# 12_Clock_2.net
KiCad netlist of a schematic drawn in Altium Designer
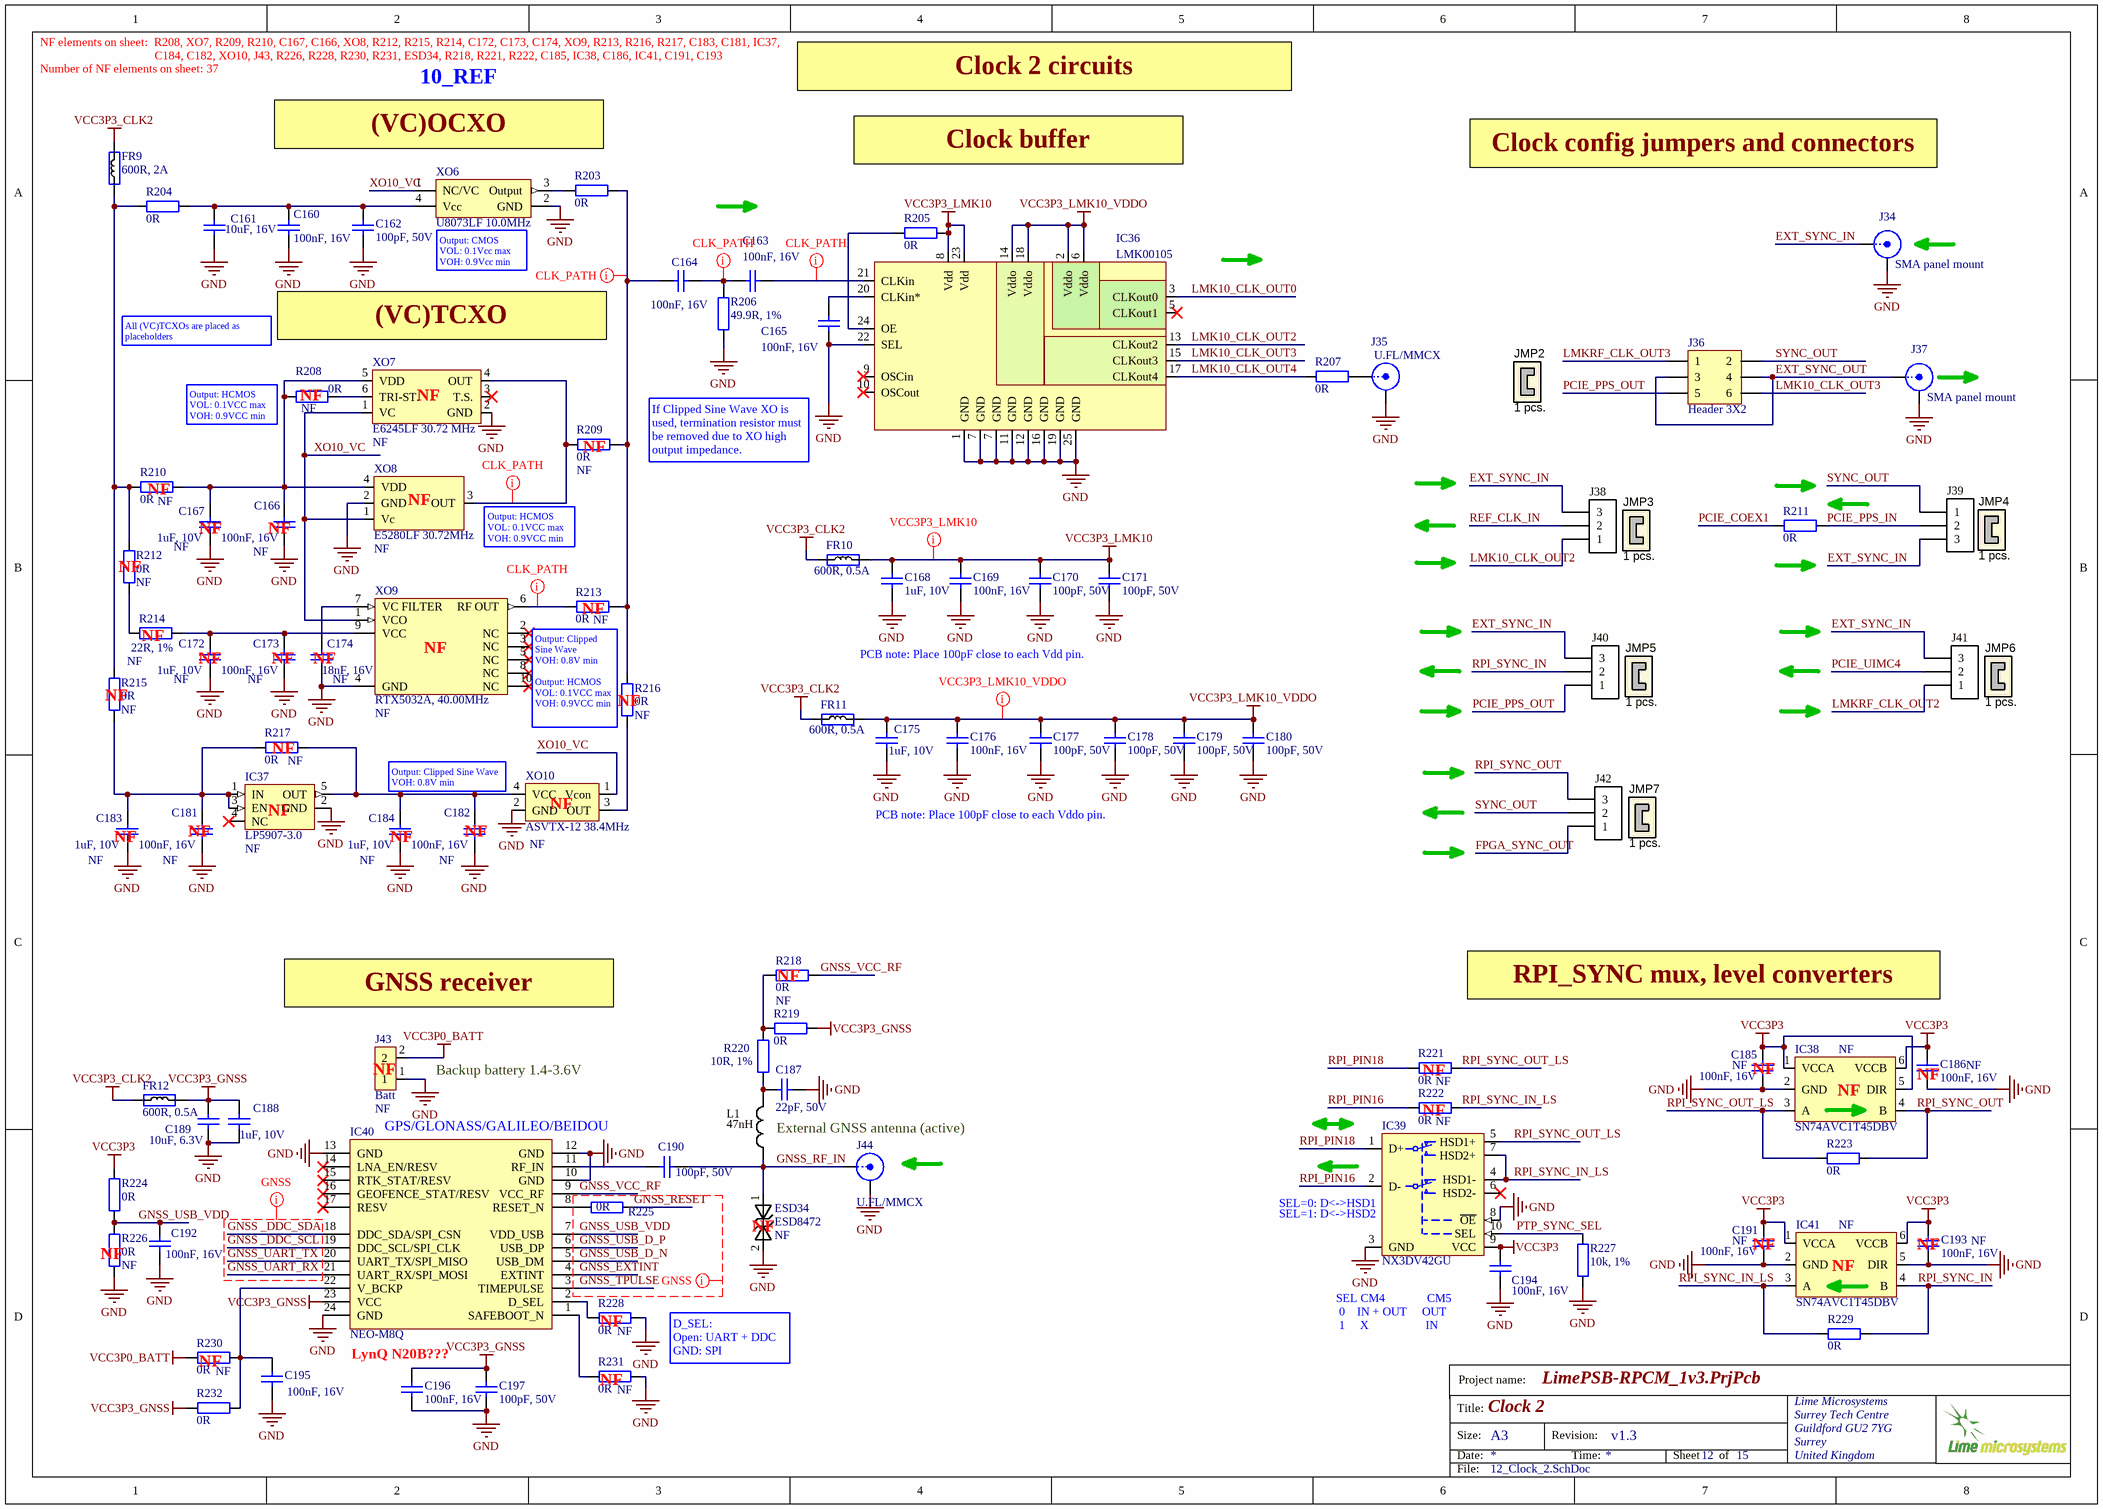
[diagram p0: 12_Clock_2.SchDoc]

(export (version "E")
  (design (tool "Eeschema 10.0.6"))
  (components
    (comp (ref "C160")
      (value "100nF, 16V")
      (footprint "CAP0402")
      (fields
        (field (name "MANUFACTURER") "Murata Electronics")
        (field (name "TOLERANCE") "10 %")
        (field (name "MANUFACTURER PART NUMBER") "GRM155R71C104KA88D")
      )
      (libsource (lib "LimeMicroAltiumLib_schLib") (part "Cap_0402"))
    )
    (comp (ref "C161")
      (value "10uF, 16V")
      (footprint "CAP0603")
      (fields (field (name "MANUFACTURER") "Yageo") (field (name "TOLERANCE") "±20%"))
      (libsource (lib "LimeMicroAltiumLib_schLib") (part "Cap_0603"))
    )
    (comp (ref "C162")
      (value "100pF, 50V")
      (footprint "CAP0402")
      (fields (field (name "TOLERANCE") "±5%") (field (name "MANUFACTURER") "Yageo"))
      (libsource (lib "LimeMicroAltiumLib_schLib") (part "Cap_0402"))
    )
    (comp (ref "C163")
      (value "100nF, 16V")
      (footprint "CAP0402")
      (fields
        (field (name "MANUFACTURER") "Murata Electronics")
        (field (name "TOLERANCE") "10 %")
        (field (name "MANUFACTURER PART NUMBER") "GRM155R71C104KA88D")
      )
      (libsource (lib "LimeMicroAltiumLib_schLib") (part "Cap_0402"))
    )
    (comp (ref "C164")
      (value "100nF, 16V")
      (footprint "CAP0402")
      (fields
        (field (name "MANUFACTURER") "Murata Electronics")
        (field (name "TOLERANCE") "10 %")
        (field (name "MANUFACTURER PART NUMBER") "GRM155R71C104KA88D")
      )
      (libsource (lib "LimeMicroAltiumLib_schLib") (part "Cap_0402"))
    )
    (comp (ref "C165")
      (value "100nF, 16V")
      (footprint "CAP0402")
      (fields
        (field (name "MANUFACTURER") "Murata Electronics")
        (field (name "TOLERANCE") "10 %")
        (field (name "MANUFACTURER PART NUMBER") "GRM155R71C104KA88D")
      )
      (libsource (lib "LimeMicroAltiumLib_schLib") (part "Cap_0402"))
    )
    (comp (ref "C166")
      (value "100nF, 16V")
      (footprint "CAP0402")
      (fields
        (field (name "ASSEMBLY INFO") "NF")
        (field (name "MANUFACTURER") "Murata Electronics")
        (field (name "TOLERANCE") "10 %")
        (field (name "MANUFACTURER PART NUMBER") "GRM155R71C104KA88D")
      )
      (libsource (lib "LimeMicroAltiumLib_schLib") (part "Cap_0402"))
    )
    (comp (ref "C167")
      (value "1uF, 10V")
      (footprint "CAP0402")
      (description "CAP CER 1UF 10V X5R 0402")
      (fields (field (name "ASSEMBLY INFO") "NF") (field (name "MANUFACTURER") "Yageo"))
      (libsource (lib "LimeMicroAltiumLib_schLib") (part "Cap_0402"))
    )
    (comp (ref "C168")
      (value "1uF, 10V")
      (footprint "CAP0402")
      (description "CAP CER 1UF 10V X5R 0402")
      (fields (field (name "MANUFACTURER") "Yageo") (field (name "TOLERANCE") "±20%"))
      (libsource (lib "LimeMicroAltiumLib_schLib") (part "Cap_0402"))
    )
    (comp (ref "C169")
      (value "100nF, 16V")
      (footprint "CAP0402")
      (fields
        (field (name "MANUFACTURER") "Murata Electronics")
        (field (name "TOLERANCE") "10 %")
        (field (name "MANUFACTURER PART NUMBER") "GRM155R71C104KA88D")
      )
      (libsource (lib "LimeMicroAltiumLib_schLib") (part "Cap_0402"))
    )
    (comp (ref "C170")
      (value "100pF, 50V")
      (footprint "CAP0402")
      (fields (field (name "MANUFACTURER") "Yageo") (field (name "TOLERANCE") "±5%"))
      (libsource (lib "LimeMicroAltiumLib_schLib") (part "Cap_0402"))
    )
    (comp (ref "C171")
      (value "100pF, 50V")
      (footprint "CAP0402")
      (fields (field (name "MANUFACTURER") "Yageo") (field (name "TOLERANCE") "±5%"))
      (libsource (lib "LimeMicroAltiumLib_schLib") (part "Cap_0402"))
    )
    (comp (ref "C172")
      (value "1uF, 10V")
      (footprint "CAP0402")
      (description "CAP CER 1UF 10V X5R 0402")
      (fields (field (name "ASSEMBLY INFO") "NF") (field (name "MANUFACTURER") "Yageo"))
      (libsource (lib "LimeMicroAltiumLib_schLib") (part "Cap_0402"))
    )
    (comp (ref "C173")
      (value "100nF, 16V")
      (footprint "CAP0402")
      (fields
        (field (name "ASSEMBLY INFO") "NF")
        (field (name "MANUFACTURER") "Murata Electronics")
        (field (name "TOLERANCE") "10 %")
        (field (name "MANUFACTURER PART NUMBER") "GRM155R71C104KA88D")
      )
      (libsource (lib "LimeMicroAltiumLib_schLib") (part "Cap_0402"))
    )
    (comp (ref "C174")
      (value "18nF, 16V")
      (footprint "CAP0402")
      (fields
        (field (name "ASSEMBLY INFO") "NF")
        (field (name "MANUFACTURER") "Yageo")
        (field (name "TOLERANCE") "±10%")
      )
      (libsource (lib "LimeMicroAltiumLib_schLib") (part "Cap_0402"))
    )
    (comp (ref "C175")
      (value "1uF, 10V")
      (footprint "CAP0402")
      (description "CAP CER 1UF 10V X5R 0402")
      (fields (field (name "MANUFACTURER") "Yageo") (field (name "TOLERANCE") "±20%"))
      (libsource (lib "LimeMicroAltiumLib_schLib") (part "Cap_0402"))
    )
    (comp (ref "C176")
      (value "100nF, 16V")
      (footprint "CAP0402")
      (fields
        (field (name "MANUFACTURER") "Murata Electronics")
        (field (name "TOLERANCE") "10 %")
        (field (name "MANUFACTURER PART NUMBER") "GRM155R71C104KA88D")
      )
      (libsource (lib "LimeMicroAltiumLib_schLib") (part "Cap_0402"))
    )
    (comp (ref "C177")
      (value "100pF, 50V")
      (footprint "CAP0402")
      (fields (field (name "MANUFACTURER") "Yageo") (field (name "TOLERANCE") "±5%"))
      (libsource (lib "LimeMicroAltiumLib_schLib") (part "Cap_0402"))
    )
    (comp (ref "C178")
      (value "100pF, 50V")
      (footprint "CAP0402")
      (fields (field (name "MANUFACTURER") "Yageo") (field (name "TOLERANCE") "±5%"))
      (libsource (lib "LimeMicroAltiumLib_schLib") (part "Cap_0402"))
    )
    (comp (ref "C179")
      (value "100pF, 50V")
      (footprint "CAP0402")
      (fields (field (name "MANUFACTURER") "Yageo") (field (name "TOLERANCE") "±5%"))
      (libsource (lib "LimeMicroAltiumLib_schLib") (part "Cap_0402"))
    )
    (comp (ref "C180")
      (value "100pF, 50V")
      (footprint "CAP0402")
      (fields (field (name "MANUFACTURER") "Yageo") (field (name "TOLERANCE") "±5%"))
      (libsource (lib "LimeMicroAltiumLib_schLib") (part "Cap_0402"))
    )
    (comp (ref "C181")
      (value "100nF, 16V")
      (footprint "CAP0402")
      (fields
        (field (name "ASSEMBLY INFO") "NF")
        (field (name "MANUFACTURER") "Murata Electronics")
        (field (name "TOLERANCE") "10 %")
        (field (name "MANUFACTURER PART NUMBER") "GRM155R71C104KA88D")
      )
      (libsource (lib "") (part "Cap_0402_1"))
    )
    (comp (ref "C182")
      (value "100nF, 16V")
      (footprint "CAP0402")
      (fields
        (field (name "ASSEMBLY INFO") "NF")
        (field (name "MANUFACTURER") "Murata Electronics")
        (field (name "TOLERANCE") "10 %")
        (field (name "MANUFACTURER PART NUMBER") "GRM155R71C104KA88D")
      )
      (libsource (lib "") (part "Cap_0402_1"))
    )
    (comp (ref "C183")
      (value "1uF, 10V")
      (footprint "CAP0402")
      (fields (field (name "ASSEMBLY INFO") "NF") (field (name "MANUFACTURER") "Yageo"))
      (libsource (lib "") (part "Cap_0402_1"))
    )
    (comp (ref "C184")
      (value "1uF, 10V")
      (footprint "CAP0402")
      (fields (field (name "ASSEMBLY INFO") "NF") (field (name "MANUFACTURER") "Yageo"))
      (libsource (lib "") (part "Cap_0402_1"))
    )
    (comp (ref "C185")
      (value "100nF, 16V")
      (footprint "CAP0402")
      (fields
        (field (name "ASSEMBLY INFO") "NF")
        (field (name "MANUFACTURER") "Murata Electronics")
        (field (name "TOLERANCE") "10 %")
        (field (name "MANUFACTURER PART NUMBER") "GRM155R71C104KA88D")
      )
      (libsource (lib "LimeMicroAltiumLib_schLib") (part "Cap_0402"))
    )
    (comp (ref "C186")
      (value "100nF, 16V")
      (footprint "CAP0402")
      (fields
        (field (name "ASSEMBLY INFO") "NF")
        (field (name "MANUFACTURER") "Murata Electronics")
        (field (name "TOLERANCE") "10 %")
        (field (name "MANUFACTURER PART NUMBER") "GRM155R71C104KA88D")
      )
      (libsource (lib "LimeMicroAltiumLib_schLib") (part "Cap_0402"))
    )
    (comp (ref "C187")
      (value "22pF, 50V")
      (footprint "CAP0402")
      (fields (field (name "TOLERANCE") "±5%") (field (name "MANUFACTURER") "Yageo"))
      (libsource (lib "LimeMicroAltiumLib_schLib") (part "Cap_0402"))
    )
    (comp (ref "C188")
      (value "1uF, 10V")
      (footprint "CAP0402")
      (description "CAP CER 1UF 10V X5R 0402")
      (fields (field (name "MANUFACTURER") "Yageo") (field (name "TOLERANCE") "±20%"))
      (libsource (lib "LimeMicroAltiumLib_schLib") (part "Cap_0402"))
    )
    (comp (ref "C189")
      (value "10uF, 6.3V")
      (footprint "CAP0603")
      (fields (field (name "TOLERANCE") "±20%") (field (name "MANUFACTURER") "Yageo"))
      (libsource (lib "LimeFPGAboard_schLib") (part "Cap_0603"))
    )
    (comp (ref "C190")
      (value "100pF, 50V")
      (footprint "CAP0402")
      (fields (field (name "TOLERANCE") "±5%") (field (name "MANUFACTURER") "Yageo"))
      (libsource (lib "LimeMicroAltiumLib_schLib") (part "Cap_0402"))
    )
    (comp (ref "C191")
      (value "100nF, 16V")
      (footprint "CAP0402")
      (fields
        (field (name "ASSEMBLY INFO") "NF")
        (field (name "MANUFACTURER") "Murata Electronics")
        (field (name "TOLERANCE") "10 %")
        (field (name "MANUFACTURER PART NUMBER") "GRM155R71C104KA88D")
      )
      (libsource (lib "LimeMicroAltiumLib_schLib") (part "Cap_0402"))
    )
    (comp (ref "C192")
      (value "100nF, 16V")
      (footprint "CAP0402")
      (fields
        (field (name "TOLERANCE") "10 %")
        (field (name "MANUFACTURER") "Murata Electronics")
        (field (name "MANUFACTURER PART NUMBER") "GRM155R71C104KA88D")
      )
      (libsource (lib "LimeFPGAboard_schLib") (part "Cap_0603"))
    )
    (comp (ref "C193")
      (value "100nF, 16V")
      (footprint "CAP0402")
      (fields
        (field (name "ASSEMBLY INFO") "NF")
        (field (name "MANUFACTURER") "Murata Electronics")
        (field (name "TOLERANCE") "10 %")
        (field (name "MANUFACTURER PART NUMBER") "GRM155R71C104KA88D")
      )
      (libsource (lib "LimeMicroAltiumLib_schLib") (part "Cap_0402"))
    )
    (comp (ref "C194")
      (value "100nF, 16V")
      (footprint "CAP0402")
      (fields
        (field (name "MANUFACTURER") "Murata Electronics")
        (field (name "TOLERANCE") "10 %")
        (field (name "MANUFACTURER PART NUMBER") "GRM155R71C104KA88D")
      )
      (libsource (lib "LimeMicroAltiumLib_schLib") (part "Cap_0402"))
    )
    (comp (ref "C195")
      (value "100nF, 16V")
      (footprint "CAP0402")
      (fields
        (field (name "TOLERANCE") "10 %")
        (field (name "MANUFACTURER") "Murata Electronics")
        (field (name "MANUFACTURER PART NUMBER") "GRM155R71C104KA88D")
      )
      (libsource (lib "LimeFPGAboard_schLib") (part "Cap_0603"))
    )
    (comp (ref "C196")
      (value "100nF, 16V")
      (footprint "CAP0402")
      (fields
        (field (name "MANUFACTURER") "Murata Electronics")
        (field (name "TOLERANCE") "10 %")
        (field (name "MANUFACTURER PART NUMBER") "GRM155R71C104KA88D")
      )
      (libsource (lib "LimeMicroAltiumLib_schLib") (part "Cap_0402"))
    )
    (comp (ref "C197")
      (value "100pF, 50V")
      (footprint "CAP0402")
      (fields (field (name "TOLERANCE") "±5%") (field (name "MANUFACTURER") "Yageo"))
      (libsource (lib "LimeMicroAltiumLib_schLib") (part "Cap_0402"))
    )
    (comp (ref "ESD34")
      (value "ESD8472")
      (footprint "ESD8472_X3DFN2")
      (fields
        (field (name "MANUFACTURER") "ON Semiconductor")
        (field (name "MANUFACTURER PART NUMBER") "ESD8472MUT5G")
        (field (name "ASSEMBLY INFO") "NF")
      )
      (libsource (lib "LimeMicroAltiumLib_schLib") (part "ESD8472"))
    )
    (comp (ref "FR9")
      (value "600R, 2A")
      (footprint "RES0805")
      (fields (field (name "MANUFACTURER") "TDK Corporation"))
      (libsource (lib "LimeFPGAboard_schLib") (part "Ferrite"))
    )
    (comp (ref "FR10")
      (value "600R, 0.5A")
      (footprint "RES0402")
      (fields (field (name "MANUFACTURER") "Murata") (field (name "TOLERANCE") "25%"))
      (libsource (lib "LimeMicroAltiumLib_schLib") (part "Ferrite"))
    )
    (comp (ref "FR11")
      (value "600R, 0.5A")
      (footprint "RES0402")
      (fields (field (name "MANUFACTURER") "Murata") (field (name "TOLERANCE") "25%"))
      (libsource (lib "LimeMicroAltiumLib_schLib") (part "Ferrite"))
    )
    (comp (ref "FR12")
      (value "600R, 0.5A")
      (footprint "RES0402")
      (fields (field (name "MANUFACTURER") "Murata") (field (name "TOLERANCE") "25%"))
      (libsource (lib "LimeMicroAltiumLib_schLib") (part "Ferrite"))
    )
    (comp (ref "IC36")
      (value "LMK00105")
      (footprint "LMK00105SQ")
      (fields (field (name "MANUFACTURER") "Texas Instruments"))
      (libsource (lib "LimeMicroAltiumLib_schLib") (part "LMK00105"))
    )
    (comp (ref "IC37")
      (value "LP5907-3.0")
      (footprint "SOT23-5")
      (fields (field (name "MANUFACTURER") "Texas Instruments") (field (name "ASSEMBLY INFO") "NF"))
      (libsource (lib "LimeMicroAltiumLib_schLib_r01") (part "LP5907"))
    )
    (comp (ref "IC38")
      (value "SN74AVC1T45DBV")
      (footprint "SOT23-6")
      (fields (field (name "ASSEMBLY INFO") "NF") (field (name "MANUFACTURER") "Texas Instruments"))
      (libsource (lib "LimeMicroAltiumLib_schLib_r04") (part "SN74AVC1T45DBV"))
    )
    (comp (ref "IC39")
      (value "NX3DV42GU")
      (footprint "FSUSB42UMX")
      (fields (field (name "MANUFACTURER") "NXP Semiconductors"))
      (libsource (lib "LimeMicroAltiumLib_schLib_r01") (part "FSUSB42UMX"))
    )
    (comp (ref "IC40")
      (value "NEO-M8Q")
      (footprint "NEO-7M/8M")
      (description "GNSS engine for GPS/QZSS, GLONASS")
      (fields (field (name "MANUFACTURER") "U-blox"))
      (libsource (lib "LimeMicroAltiumLib_schLib") (part "NEO-M8P_M8M"))
    )
    (comp (ref "IC41")
      (value "SN74AVC1T45DBV")
      (footprint "SOT23-6")
      (fields (field (name "ASSEMBLY INFO") "NF") (field (name "MANUFACTURER") "Texas Instruments"))
      (libsource (lib "LimeMicroAltiumLib_schLib_r04") (part "SN74AVC1T45DBV"))
    )
    (comp (ref "J34")
      (value "SMA panel mount")
      (footprint "SMA_connector_side")
      (description "CONN SMA JACK STR 50OHM EDGE MNT")
      (fields (field (name "MANUFACTURER") "Linx"))
      (libsource (lib "LimeMicroAltiumLib_schLib") (part "RF_IF_connector"))
    )
    (comp (ref "J35")
      (value "U.FL/MMCX")
      (footprint "MMCX_UFL_conn_u")
      (description "CONN UMC RCPT STR 50 OHM SMD")
      (fields (field (name "MANUFACTURER") "Molex, LLC"))
      (libsource (lib "") (part "RF_IF_connector_1"))
    )
    (comp (ref "J36")
      (value "Header 3X2")
      (footprint "Header3x2")
      (description "Header, 2-Pin, Dual row")
      (fields
        (field (name "MANUFACTURER PART NUMBER") "PH2-06-UA")
        (field (name "MANUFACTURER") "Adam Equipment")
      )
      (libsource (lib "LimeMicroAltiumLib_schLib_r01") (part "Header 3X2"))
    )
    (comp (ref "J37")
      (value "SMA panel mount")
      (footprint "SMA_connector_side")
      (description "CONN SMA JACK STR 50OHM EDGE MNT")
      (fields (field (name "MANUFACTURER") "Linx"))
      (libsource (lib "LimeMicroAltiumLib_schLib") (part "RF_IF_connector"))
    )
    (comp (ref "J38")
      (value "Header 3x1 pin")
      (footprint "HDR_1x3")
      (description "Header, 3-pin")
      (fields
        (field (name "MANUFACTURER PART NUMBER") "61300311121")
        (field (name "MANUFACTURER") "Wurth Electronics")
      )
      (libsource (lib "LimeMicroAltiumLib_schLib_r04") (part "Header3P"))
    )
    (comp (ref "J39")
      (value "Header 3x1 pin")
      (footprint "HDR_1x3")
      (description "Header, 3-pin")
      (fields
        (field (name "MANUFACTURER PART NUMBER") "61300311121")
        (field (name "MANUFACTURER") "Wurth Electronics")
      )
      (libsource (lib "") (part "Header3P_1"))
    )
    (comp (ref "J40")
      (value "Header 3x1 pin")
      (footprint "HDR_1x3")
      (description "Header, 3-pin")
      (fields
        (field (name "MANUFACTURER PART NUMBER") "61300311121")
        (field (name "MANUFACTURER") "Wurth Electronics")
      )
      (libsource (lib "LimeMicroAltiumLib_schLib_r04") (part "Header3P"))
    )
    (comp (ref "J41")
      (value "Header 3x1 pin")
      (footprint "HDR_1x3")
      (description "Header, 3-pin")
      (fields
        (field (name "MANUFACTURER PART NUMBER") "61300311121")
        (field (name "MANUFACTURER") "Wurth Electronics")
      )
      (libsource (lib "LimeMicroAltiumLib_schLib_r04") (part "Header3P"))
    )
    (comp (ref "J42")
      (value "Header 3x1 pin")
      (footprint "HDR_1x3")
      (description "Header, 3-pin")
      (fields
        (field (name "MANUFACTURER PART NUMBER") "61300311121")
        (field (name "MANUFACTURER") "Wurth Electronics")
      )
      (libsource (lib "LimeMicroAltiumLib_schLib_r04") (part "Header3P"))
    )
    (comp (ref "J43")
      (value "Batt")
      (footprint "HDR_1x2")
      (fields (field (name "ASSEMBLY INFO") "NF") (field (name "MANUFACTURER") "3M"))
      (libsource (lib "LimeFPGAboard_schLib") (part "Jumper"))
    )
    (comp (ref "J44")
      (value "U.FL/MMCX")
      (footprint "MMCX_UFL_conn_u")
      (description "CONN UMC RCPT STR 50 OHM SMD")
      (fields (field (name "MANUFACTURER") "Molex, LLC"))
      (libsource (lib "") (part "RF_IF_connector_1"))
    )
    (comp (ref "JMP2")
      (value "1 pcs.")
      (description "Shorting Jumper, 2-position, 1.27mm pitch")
      (fields (field (name "MANUFACTURER") "Sullins"))
      (libsource (lib "LimeMicroAltiumLib_schLib") (part "JUMP_2P_CONN_HEADER"))
    )
    (comp (ref "JMP3")
      (value "1 pcs.")
      (description "Shorting Jumper, 2-position, 1.27mm pitch")
      (fields (field (name "MANUFACTURER") "Sullins"))
      (libsource (lib "LimeMicroAltiumLib_schLib") (part "JUMP_2P_CONN_HEADER"))
    )
    (comp (ref "JMP4")
      (value "1 pcs.")
      (description "Shorting Jumper, 2-position, 1.27mm pitch")
      (fields (field (name "MANUFACTURER") "Sullins"))
      (libsource (lib "LimeMicroAltiumLib_schLib") (part "JUMP_2P_CONN_HEADER"))
    )
    (comp (ref "JMP5")
      (value "1 pcs.")
      (description "Shorting Jumper, 2-position, 1.27mm pitch")
      (fields (field (name "MANUFACTURER") "Sullins"))
      (libsource (lib "LimeMicroAltiumLib_schLib") (part "JUMP_2P_CONN_HEADER"))
    )
    (comp (ref "JMP6")
      (value "1 pcs.")
      (description "Shorting Jumper, 2-position, 1.27mm pitch")
      (fields (field (name "MANUFACTURER") "Sullins"))
      (libsource (lib "LimeMicroAltiumLib_schLib") (part "JUMP_2P_CONN_HEADER"))
    )
    (comp (ref "JMP7")
      (value "1 pcs.")
      (description "Shorting Jumper, 2-position, 1.27mm pitch")
      (fields (field (name "MANUFACTURER") "Sullins"))
      (libsource (lib "LimeMicroAltiumLib_schLib") (part "JUMP_2P_CONN_HEADER"))
    )
    (comp (ref "L1")
      (value "47nH")
      (footprint "RES0402")
      (fields
        (field (name "MANUFACTURER") "COILCRAFT")
        (field (name "MANUFACTURER PART NUMBER") "0402HP-47NXJLU")
      )
      (libsource (lib "LimeMicroAltiumLib_schLib") (part "Inductor_0603"))
    )
    (comp (ref "R203")
      (value "0R")
      (footprint "RES0402_v2")
      (fields (field (name "MANUFACTURER") "Yageo") (field (name "TOLERANCE") "Jumper"))
      (libsource (lib "LimeMicroAltiumLib_schLib") (part "Res_0402"))
    )
    (comp (ref "R204")
      (value "0R")
      (footprint "RES0402")
      (fields (field (name "MANUFACTURER") "Yageo") (field (name "TOLERANCE") "Jumper"))
      (libsource (lib "LimeMicroAltiumLib_schLib") (part "Res_0402"))
    )
    (comp (ref "R205")
      (value "0R")
      (footprint "RES0402")
      (fields (field (name "MANUFACTURER") "Yageo") (field (name "TOLERANCE") "Jumper"))
      (libsource (lib "LimeMicroAltiumLib_schLib") (part "Res_0402"))
    )
    (comp (ref "R206")
      (value "49.9R, 1%")
      (footprint "RES0402")
      (fields
        (field (name "TOLERANCE") "±1%")
        (field (name "MANUFACTURER") "Samsung Electro-Mechanics America, Inc.")
      )
      (libsource (lib "LimeMicroAltiumLib_schLib") (part "Res_0402"))
    )
    (comp (ref "R207")
      (value "0R")
      (footprint "RES0402")
      (fields (field (name "MANUFACTURER") "Yageo") (field (name "TOLERANCE") "Jumper"))
      (libsource (lib "") (part "Res_0402_1"))
    )
    (comp (ref "R208")
      (value "0R")
      (footprint "RES0402")
      (fields
        (field (name "ASSEMBLY INFO") "NF")
        (field (name "MANUFACTURER") "Yageo")
        (field (name "TOLERANCE") "Jumper")
      )
      (libsource (lib "LimeMicroAltiumLib_schLib") (part "Res_0402"))
    )
    (comp (ref "R209")
      (value "0R")
      (footprint "RES0402_v2")
      (fields
        (field (name "ASSEMBLY INFO") "NF")
        (field (name "MANUFACTURER") "Yageo")
        (field (name "TOLERANCE") "Jumper")
      )
      (libsource (lib "LimeMicroAltiumLib_schLib") (part "Res_0402"))
    )
    (comp (ref "R210")
      (value "0R")
      (footprint "RES0402")
      (fields
        (field (name "MANUFACTURER") "Yageo")
        (field (name "TOLERANCE") "Jumper")
        (field (name "ASSEMBLY INFO") "NF")
      )
      (libsource (lib "LimeMicroAltiumLib_schLib") (part "Res_0402"))
    )
    (comp (ref "R211")
      (value "0R")
      (footprint "RES0402")
      (fields (field (name "MANUFACTURER") "Yageo") (field (name "TOLERANCE") "Jumper"))
      (libsource (lib "") (part "Res_0402_1"))
    )
    (comp (ref "R212")
      (value "0R")
      (footprint "RES0402")
      (fields
        (field (name "ASSEMBLY INFO") "NF")
        (field (name "MANUFACTURER") "Yageo")
        (field (name "TOLERANCE") "Jumper")
      )
      (libsource (lib "LimeMicroAltiumLib_schLib") (part "Res_0402"))
    )
    (comp (ref "R213")
      (value "0R")
      (footprint "RES0402_v2")
      (fields
        (field (name "ASSEMBLY INFO") "NF")
        (field (name "MANUFACTURER") "Yageo")
        (field (name "TOLERANCE") "Jumper")
      )
      (libsource (lib "LimeMicroAltiumLib_schLib") (part "Res_0402"))
    )
    (comp (ref "R214")
      (value "22R, 1%")
      (footprint "RES0402")
      (fields
        (field (name "TOLERANCE") "±1%")
        (field (name "MANUFACTURER") "Yageo")
        (field (name "ASSEMBLY INFO") "NF")
      )
      (libsource (lib "LimeFPGAboard_schLib") (part "Res_0402"))
    )
    (comp (ref "R215")
      (value "0R")
      (footprint "RES0402")
      (fields
        (field (name "MANUFACTURER") "Yageo")
        (field (name "TOLERANCE") "Jumper")
        (field (name "ASSEMBLY INFO") "NF")
      )
      (libsource (lib "") (part "Res_0402_1"))
    )
    (comp (ref "R216")
      (value "0R")
      (footprint "RES0402_v2")
      (fields
        (field (name "ASSEMBLY INFO") "NF")
        (field (name "MANUFACTURER") "Yageo")
        (field (name "TOLERANCE") "Jumper")
      )
      (libsource (lib "") (part "Res_0402_1"))
    )
    (comp (ref "R217")
      (value "0R")
      (footprint "RES0402")
      (fields
        (field (name "MANUFACTURER") "Yageo")
        (field (name "TOLERANCE") "Jumper")
        (field (name "ASSEMBLY INFO") "NF")
      )
      (libsource (lib "") (part "Res_0402_1"))
    )
    (comp (ref "R218")
      (value "0R")
      (footprint "RES0402")
      (fields
        (field (name "ASSEMBLY INFO") "NF")
        (field (name "MANUFACTURER") "Yageo")
        (field (name "TOLERANCE") "Jumper")
      )
      (libsource (lib "LimeMicroAltiumLib_schLib") (part "Res_0402"))
    )
    (comp (ref "R219")
      (value "0R")
      (footprint "RES0402")
      (fields (field (name "MANUFACTURER") "Yageo") (field (name "TOLERANCE") "Jumper"))
      (libsource (lib "LimeMicroAltiumLib_schLib") (part "Res_0402"))
    )
    (comp (ref "R220")
      (value "10R, 1%")
      (footprint "RES0402")
      (fields (field (name "MANUFACTURER") "Stackpole Electronics") (field (name "TOLERANCE") "1%"))
      (libsource (lib "LimeMicroAltiumLib_schLib") (part "Res_0402"))
    )
    (comp (ref "R221")
      (value "0R")
      (footprint "RES0402")
      (fields
        (field (name "ASSEMBLY INFO") "NF")
        (field (name "MANUFACTURER") "Yageo")
        (field (name "TOLERANCE") "Jumper")
      )
      (libsource (lib "") (part "Res_0402_1"))
    )
    (comp (ref "R222")
      (value "0R")
      (footprint "RES0402")
      (fields
        (field (name "ASSEMBLY INFO") "NF")
        (field (name "MANUFACTURER") "Yageo")
        (field (name "TOLERANCE") "Jumper")
      )
      (libsource (lib "") (part "Res_0402_1"))
    )
    (comp (ref "R223")
      (value "0R")
      (footprint "RES0402")
      (fields (field (name "MANUFACTURER") "Yageo") (field (name "TOLERANCE") "Jumper"))
      (libsource (lib "LimeFPGAboard_schLib") (part "Res_0402"))
    )
    (comp (ref "R224")
      (value "0R")
      (footprint "RES0402")
      (fields (field (name "MANUFACTURER") "Yageo") (field (name "TOLERANCE") "Jumper"))
      (libsource (lib "LimeMicroAltiumLib_schLib") (part "Res_0402"))
    )
    (comp (ref "R225")
      (value "0R")
      (footprint "RES0402")
      (fields (field (name "MANUFACTURER") "Yageo") (field (name "TOLERANCE") "Jumper"))
      (libsource (lib "LimeMicroAltiumLib_schLib") (part "Res_0402"))
    )
    (comp (ref "R226")
      (value "0R")
      (footprint "RES0402")
      (fields
        (field (name "ASSEMBLY INFO") "NF")
        (field (name "MANUFACTURER") "Yageo")
        (field (name "TOLERANCE") "Jumper")
      )
      (libsource (lib "LimeMicroAltiumLib_schLib") (part "Res_0402"))
    )
    (comp (ref "R227")
      (value "10k, 1%")
      (footprint "RES0402")
      (fields (field (name "MANUFACTURER") "Yageo") (field (name "TOLERANCE") "±1%"))
      (libsource (lib "LimeMicroAltiumLib_schLib") (part "Res_0402"))
    )
    (comp (ref "R228")
      (value "0R")
      (footprint "RES0402")
      (fields
        (field (name "ASSEMBLY INFO") "NF")
        (field (name "MANUFACTURER") "Yageo")
        (field (name "TOLERANCE") "Jumper")
      )
      (libsource (lib "LimeMicroAltiumLib_schLib") (part "Res_0402"))
    )
    (comp (ref "R229")
      (value "0R")
      (footprint "RES0402")
      (fields (field (name "MANUFACTURER") "Yageo") (field (name "TOLERANCE") "Jumper"))
      (libsource (lib "LimeFPGAboard_schLib") (part "Res_0402"))
    )
    (comp (ref "R230")
      (value "0R")
      (footprint "RES0402")
      (fields
        (field (name "ASSEMBLY INFO") "NF")
        (field (name "MANUFACTURER") "Yageo")
        (field (name "TOLERANCE") "Jumper")
      )
      (libsource (lib "LimeMicroAltiumLib_schLib") (part "Res_0402"))
    )
    (comp (ref "R231")
      (value "0R")
      (footprint "RES0402")
      (fields
        (field (name "ASSEMBLY INFO") "NF")
        (field (name "MANUFACTURER") "Yageo")
        (field (name "TOLERANCE") "Jumper")
      )
      (libsource (lib "LimeMicroAltiumLib_schLib") (part "Res_0402"))
    )
    (comp (ref "R232")
      (value "0R")
      (footprint "RES0402")
      (fields (field (name "MANUFACTURER") "Yageo") (field (name "TOLERANCE") "Jumper"))
      (libsource (lib "LimeMicroAltiumLib_schLib") (part "Res_0402"))
    )
    (comp (ref "XO6")
      (value "U8073LF 10.0MHz")
      (footprint "AOCJYR-10.000MHz")
      (fields (field (name "MANUFACTURER") "Rakon"))
      (libsource (lib "LimeMicroAltiumLib_schLib") (part "AOCJYR-10.000MHz"))
    )
    (comp (ref "XO7")
      (value "E6245LF 30.72 MHz")
      (footprint "RAKON_RPT7050A")
      (fields (field (name "ASSEMBLY INFO") "NF") (field (name "MANUFACTURER") "Rakon"))
      (libsource (lib "LimeMicroAltiumLib_schLib") (part "RPT7050A"))
    )
    (comp (ref "XO8")
      (value "E5280LF 30.72MHz")
      (footprint "RAKON_TXCO")
      (fields (field (name "ASSEMBLY INFO") "NF") (field (name "MANUFACTURER") "Rakon"))
      (libsource (lib "LimeMicroAltiumLib_schLib") (part "TXCO"))
    )
    (comp (ref "XO9")
      (value "RTX5032A, 40.00MHz")
      (footprint "RAKON_RTX5032A")
      (fields (field (name "ASSEMBLY INFO") "NF") (field (name "MANUFACTURER") "Rakon"))
      (libsource (lib "LimeMicroAltiumLib_schLib") (part "Rakon_RTX5032A"))
    )
    (comp (ref "XO10")
      (value "ASVTX-12 38.4MHz")
      (footprint "CRYSTAL_4-LCC_2P5x2P0")
      (description "Oscillator Crystal")
      (fields (field (name "MANUFACTURER") "Abracon") (field (name "ASSEMBLY INFO") "NF"))
      (libsource (lib "LimeMicroAltiumLib_schLib_r01") (part "ASVTX-12-A-38.400MHZ-H10-T_CRYSTAL"))
    )
  )
  (nets
    (net (code "1") (name "/EXT_SYNC_IN") (class "Default")
      (node (ref "J34") (pin "1") (pinfunction "X_1") (pintype "passive"))
      (node (ref "J38") (pin "3") (pinfunction "3_3") (pintype "passive"))
      (node (ref "J39") (pin "3") (pinfunction "3_3") (pintype "passive"))
      (node (ref "J40") (pin "3") (pinfunction "3_3") (pintype "passive"))
      (node (ref "J41") (pin "3") (pinfunction "3_3") (pintype "passive"))
    )
    (net (code "2") (name "/EXT_SYNC_OUT") (class "Default")
      (node (ref "J36") (pin "3") (pinfunction "3_3") (pintype "passive"))
      (node (ref "J36") (pin "4") (pinfunction "4_4") (pintype "passive"))
      (node (ref "J37") (pin "1") (pinfunction "X_1") (pintype "passive"))
    )
    (net (code "3") (name "/FPGA_SYNC_OUT") (class "Default")
      (node (ref "J42") (pin "1") (pinfunction "1_1") (pintype "passive"))
    )
    (net (code "4") (name "/GNSS _DDC_SCL") (class "Default")
      (node (ref "IC40") (pin "19") (pinfunction "DDC_SCL/SPI_CLK_19") (pintype "passive"))
    )
    (net (code "5") (name "/GNSS _DDC_SDA") (class "Default")
      (node (ref "IC40") (pin "18") (pinfunction "DDC_SDA/SPI_CSN_18") (pintype "passive"))
    )
    (net (code "6") (name "/GNSS_EXTINT") (class "Default")
      (node (ref "IC40") (pin "4") (pinfunction "EXTINT_4") (pintype "passive"))
    )
    (net (code "7") (name "/GNSS_RESET") (class "Default")
      (node (ref "R225") (pin "1") (pinfunction "1_1") (pintype "passive"))
    )
    (net (code "8") (name "/GNSS_RF_IN") (class "Default")
      (node (ref "C190") (pin "1") (pinfunction "1_1") (pintype "passive"))
      (node (ref "ESD34") (pin "1") (pinfunction "1_1") (pintype "passive"))
      (node (ref "J44") (pin "1") (pinfunction "X_1") (pintype "passive"))
      (node (ref "L1") (pin "1") (pinfunction "1_1") (pintype "passive"))
    )
    (net (code "9") (name "/GNSS_TPULSE") (class "Default")
      (node (ref "IC40") (pin "3") (pinfunction "TIMEPULSE_3") (pintype "passive"))
    )
    (net (code "10") (name "/GNSS_UART_RX") (class "Default")
      (node (ref "IC40") (pin "21") (pinfunction "UART_RX/SPI_MOSI_21") (pintype "passive"))
    )
    (net (code "11") (name "/GNSS_UART_TX") (class "Default")
      (node (ref "IC40") (pin "20") (pinfunction "UART_TX/SPI_MISO_20") (pintype "passive"))
    )
    (net (code "12") (name "/GNSS_USB_D_N") (class "Default")
      (node (ref "IC40") (pin "5") (pinfunction "USB_DM_5") (pintype "passive"))
    )
    (net (code "13") (name "/GNSS_USB_D_P") (class "Default")
      (node (ref "IC40") (pin "6") (pinfunction "USB_DP_6") (pintype "passive"))
    )
    (net (code "14") (name "/GNSS_USB_VDD") (class "Default")
      (node (ref "C192") (pin "1") (pinfunction "1_1") (pintype "passive"))
      (node (ref "IC40") (pin "7") (pinfunction "VDD_USB_7") (pintype "passive"))
      (node (ref "R224") (pin "2") (pinfunction "2_2") (pintype "passive"))
      (node (ref "R226") (pin "2") (pinfunction "2_2") (pintype "passive"))
    )
    (net (code "15") (name "/GNSS_VCC_RF") (class "Default")
      (node (ref "IC40") (pin "9") (pinfunction "VCC_RF_9") (pintype "passive"))
      (node (ref "R218") (pin "2") (pinfunction "2_2") (pintype "passive"))
    )
    (net (code "16") (name "/LMK10_CLK_OUT0") (class "Default")
      (node (ref "IC36") (pin "3") (pinfunction "CLKout0_3") (pintype "passive"))
    )
    (net (code "17") (name "/LMK10_CLK_OUT2") (class "Default")
      (node (ref "IC36") (pin "13") (pinfunction "CLKout2_13") (pintype "passive"))
      (node (ref "J38") (pin "1") (pinfunction "1_1") (pintype "passive"))
    )
    (net (code "18") (name "/LMK10_CLK_OUT3") (class "Default")
      (node (ref "IC36") (pin "15") (pinfunction "CLKout3_15") (pintype "passive"))
      (node (ref "J36") (pin "6") (pinfunction "6_6") (pintype "passive"))
    )
    (net (code "19") (name "/LMK10_CLK_OUT4") (class "Default")
      (node (ref "IC36") (pin "17") (pinfunction "CLKout4_17") (pintype "passive"))
      (node (ref "R207") (pin "2") (pinfunction "2_2") (pintype "passive"))
    )
    (net (code "20") (name "/LMKRF_CLK_OUT2") (class "Default")
      (node (ref "J41") (pin "1") (pinfunction "1_1") (pintype "passive"))
    )
    (net (code "21") (name "/LMKRF_CLK_OUT3") (class "Default")
      (node (ref "J36") (pin "1") (pinfunction "1_1") (pintype "passive"))
    )
    (net (code "22") (name "/PCIE_COEX1") (class "Default")
      (node (ref "R211") (pin "2") (pinfunction "2_2") (pintype "passive"))
    )
    (net (code "24") (name "/PCIE_PPS_OUT") (class "Default")
      (node (ref "J36") (pin "5") (pinfunction "5_5") (pintype "passive"))
      (node (ref "J40") (pin "1") (pinfunction "1_1") (pintype "passive"))
    )
    (net (code "25") (name "/PCIE_UIMC4") (class "Default")
      (node (ref "J41") (pin "2") (pinfunction "2_2") (pintype "passive"))
    )
    (net (code "26") (name "/PTP_SYNC_SEL") (class "Default")
      (node (ref "IC39") (pin "10") (pinfunction "SEL_10") (pintype "input"))
      (node (ref "R227") (pin "1") (pinfunction "1_1") (pintype "passive"))
    )
    (net (code "27") (name "/REF_CLK_IN") (class "Default")
      (node (ref "J38") (pin "2") (pinfunction "2_2") (pintype "passive"))
    )
    (net (code "28") (name "/RPI_PIN16") (class "Default")
      (node (ref "IC39") (pin "2") (pinfunction "D-_2") (pintype "passive"))
      (node (ref "R222") (pin "2") (pinfunction "2_2") (pintype "passive"))
    )
    (net (code "29") (name "/RPI_PIN18") (class "Default")
      (node (ref "IC39") (pin "1") (pinfunction "D+_1") (pintype "passive"))
      (node (ref "R221") (pin "2") (pinfunction "2_2") (pintype "passive"))
    )
    (net (code "30") (name "/RPI_SYNC_IN") (class "Default")
      (node (ref "IC41") (pin "4") (pinfunction "B_4") (pintype "bidirectional"))
      (node (ref "J40") (pin "2") (pinfunction "2_2") (pintype "passive"))
      (node (ref "R229") (pin "1") (pinfunction "1_1") (pintype "passive"))
    )
    (net (code "31") (name "/RPI_SYNC_IN_LS") (class "Default")
      (node (ref "IC39") (pin "4") (pinfunction "HSD1-_4") (pintype "passive"))
      (node (ref "IC39") (pin "7") (pinfunction "HSD2+_7") (pintype "passive"))
      (node (ref "IC41") (pin "3") (pinfunction "A_3") (pintype "bidirectional"))
      (node (ref "R222") (pin "1") (pinfunction "1_1") (pintype "passive"))
      (node (ref "R229") (pin "2") (pinfunction "2_2") (pintype "passive"))
    )
    (net (code "32") (name "/RPI_SYNC_OUT") (class "Default")
      (node (ref "IC38") (pin "4") (pinfunction "B_4") (pintype "bidirectional"))
      (node (ref "J42") (pin "3") (pinfunction "3_3") (pintype "passive"))
      (node (ref "R223") (pin "1") (pinfunction "1_1") (pintype "passive"))
    )
    (net (code "33") (name "/RPI_SYNC_OUT_LS") (class "Default")
      (node (ref "IC38") (pin "3") (pinfunction "A_3") (pintype "bidirectional"))
      (node (ref "IC39") (pin "5") (pinfunction "HSD1+_5") (pintype "passive"))
      (node (ref "R221") (pin "1") (pinfunction "1_1") (pintype "passive"))
      (node (ref "R223") (pin "2") (pinfunction "2_2") (pintype "passive"))
    )
    (net (code "34") (name "/SYNC_OUT") (class "Default")
      (node (ref "J36") (pin "2") (pinfunction "2_2") (pintype "passive"))
      (node (ref "J39") (pin "1") (pinfunction "1_1") (pintype "passive"))
      (node (ref "J42") (pin "2") (pinfunction "2_2") (pintype "passive"))
    )
    (net (code "35") (name "/XO10_VC") (class "Default")
      (node (ref "XO10") (pin "1") (pinfunction "Vcon_1") (pintype "passive"))
      (node (ref "XO6") (pin "1") (pinfunction "NC/VC_1") (pintype "passive"))
      (node (ref "XO7") (pin "1") (pinfunction "VC_1") (pintype "passive"))
      (node (ref "XO8") (pin "1") (pinfunction "Vc_1") (pintype "passive"))
      (node (ref "XO9") (pin "1") (pinfunction "VCO_1") (pintype "input"))
    )
    (net (code "36") (name "GND") (class "Default")
      (node (ref "C160") (pin "1") (pinfunction "1_1") (pintype "passive"))
      (node (ref "C161") (pin "1") (pinfunction "1_1") (pintype "passive"))
      (node (ref "C162") (pin "2") (pinfunction "2_2") (pintype "passive"))
      (node (ref "C165") (pin "1") (pinfunction "1_1") (pintype "passive"))
      (node (ref "C166") (pin "1") (pinfunction "1_1") (pintype "passive"))
      (node (ref "C167") (pin "1") (pinfunction "1_1") (pintype "passive"))
      (node (ref "C168") (pin "1") (pinfunction "1_1") (pintype "passive"))
      (node (ref "C169") (pin "1") (pinfunction "1_1") (pintype "passive"))
      (node (ref "C170") (pin "1") (pinfunction "1_1") (pintype "passive"))
      (node (ref "C171") (pin "1") (pinfunction "1_1") (pintype "passive"))
      (node (ref "C172") (pin "1") (pinfunction "1_1") (pintype "passive"))
      (node (ref "C173") (pin "1") (pinfunction "1_1") (pintype "passive"))
      (node (ref "C174") (pin "1") (pinfunction "1_1") (pintype "passive"))
      (node (ref "C175") (pin "1") (pinfunction "1_1") (pintype "passive"))
      (node (ref "C176") (pin "1") (pinfunction "1_1") (pintype "passive"))
      (node (ref "C177") (pin "1") (pinfunction "1_1") (pintype "passive"))
      (node (ref "C178") (pin "1") (pinfunction "1_1") (pintype "passive"))
      (node (ref "C179") (pin "1") (pinfunction "1_1") (pintype "passive"))
      (node (ref "C180") (pin "1") (pinfunction "1_1") (pintype "passive"))
      (node (ref "C181") (pin "1") (pinfunction "1_1") (pintype "passive"))
      (node (ref "C182") (pin "1") (pinfunction "1_1") (pintype "passive"))
      (node (ref "C183") (pin "1") (pinfunction "1_1") (pintype "passive"))
      (node (ref "C184") (pin "1") (pinfunction "1_1") (pintype "passive"))
      (node (ref "C185") (pin "2") (pinfunction "2_2") (pintype "passive"))
      (node (ref "C186") (pin "2") (pinfunction "2_2") (pintype "passive"))
      (node (ref "C187") (pin "1") (pinfunction "1_1") (pintype "passive"))
      (node (ref "C188") (pin "1") (pinfunction "1_1") (pintype "passive"))
      (node (ref "C189") (pin "1") (pinfunction "1_1") (pintype "passive"))
      (node (ref "C191") (pin "2") (pinfunction "2_2") (pintype "passive"))
      (node (ref "C192") (pin "2") (pinfunction "2_2") (pintype "passive"))
      (node (ref "C193") (pin "2") (pinfunction "2_2") (pintype "passive"))
      (node (ref "C194") (pin "2") (pinfunction "2_2") (pintype "passive"))
      (node (ref "C195") (pin "2") (pinfunction "2_2") (pintype "passive"))
      (node (ref "C196") (pin "1") (pinfunction "1_1") (pintype "passive"))
      (node (ref "C197") (pin "2") (pinfunction "2_2") (pintype "passive"))
      (node (ref "ESD34") (pin "2") (pinfunction "2_2") (pintype "passive"))
      (node (ref "IC36") (pin "1") (pinfunction "GND_1") (pintype "passive"))
      (node (ref "IC36") (pin "11") (pinfunction "GND_11") (pintype "passive"))
      (node (ref "IC36") (pin "12") (pinfunction "GND_12") (pintype "passive"))
      (node (ref "IC36") (pin "16") (pinfunction "GND_16") (pintype "passive"))
      (node (ref "IC36") (pin "19") (pinfunction "GND_19") (pintype "passive"))
      (node (ref "IC36") (pin "22") (pinfunction "SEL_22") (pintype "passive"))
      (node (ref "IC36") (pin "25") (pinfunction "GND_25") (pintype "passive"))
      (node (ref "IC36") (pin "7") (pinfunction "GND_7") (pintype "passive"))
      (node (ref "IC37") (pin "2") (pinfunction "GND_2") (pintype "passive"))
      (node (ref "IC38") (pin "2") (pinfunction "GND_2") (pintype "passive"))
      (node (ref "IC39") (pin "3") (pinfunction "GND_3") (pintype "passive"))
      (node (ref "IC39") (pin "8") (pinfunction "~{OE}_8") (pintype "input"))
      (node (ref "IC40") (pin "10") (pinfunction "GND_10") (pintype "passive"))
      (node (ref "IC40") (pin "12") (pinfunction "GND_12") (pintype "passive"))
      (node (ref "IC40") (pin "13") (pinfunction "GND_13") (pintype "passive"))
      (node (ref "IC40") (pin "24") (pinfunction "GND_24") (pintype "passive"))
      (node (ref "IC41") (pin "2") (pinfunction "GND_2") (pintype "passive"))
      (node (ref "IC41") (pin "5") (pinfunction "DIR_5") (pintype "input"))
      (node (ref "J34") (pin "2") (pinfunction "Y_2") (pintype "passive"))
      (node (ref "J35") (pin "2") (pinfunction "Y_2") (pintype "passive"))
      (node (ref "J37") (pin "2") (pinfunction "Y_2") (pintype "passive"))
      (node (ref "J43") (pin "1") (pinfunction "1_1") (pintype "passive"))
      (node (ref "J44") (pin "2") (pinfunction "Y_2") (pintype "passive"))
      (node (ref "R206") (pin "1") (pinfunction "1_1") (pintype "passive"))
      (node (ref "R226") (pin "1") (pinfunction "1_1") (pintype "passive"))
      (node (ref "R227") (pin "2") (pinfunction "2_2") (pintype "passive"))
      (node (ref "R228") (pin "1") (pinfunction "1_1") (pintype "passive"))
      (node (ref "R231") (pin "1") (pinfunction "1_1") (pintype "passive"))
      (node (ref "XO10") (pin "2") (pinfunction "GND_2") (pintype "passive"))
      (node (ref "XO6") (pin "2") (pinfunction "GND_2") (pintype "passive"))
      (node (ref "XO7") (pin "2") (pinfunction "GND_2") (pintype "passive"))
      (node (ref "XO8") (pin "2") (pinfunction "GND_2") (pintype "passive"))
      (node (ref "XO9") (pin "4") (pinfunction "GND_4") (pintype "passive"))
    )
    (net (code "37") (name "Net-(C163-Pad2)") (class "Default")
      (node (ref "C163") (pin "2") (pinfunction "2_2") (pintype "passive"))
      (node (ref "C164") (pin "1") (pinfunction "1_1") (pintype "passive"))
      (node (ref "R206") (pin "2") (pinfunction "2_2") (pintype "passive"))
    )
    (net (code "38") (name "Net-(C164-Pad2)") (class "Default")
      (node (ref "C164") (pin "2") (pinfunction "2_2") (pintype "passive"))
      (node (ref "R203") (pin "1") (pinfunction "1_1") (pintype "passive"))
      (node (ref "R209") (pin "1") (pinfunction "1_1") (pintype "passive"))
      (node (ref "R213") (pin "2") (pinfunction "2_2") (pintype "passive"))
      (node (ref "R216") (pin "1") (pinfunction "1_1") (pintype "passive"))
    )
    (net (code "39") (name "Net-(C187-Pad2)") (class "Default")
      (node (ref "C187") (pin "2") (pinfunction "2_2") (pintype "passive"))
      (node (ref "L1") (pin "2") (pinfunction "2_2") (pintype "passive"))
      (node (ref "R220") (pin "1") (pinfunction "1_1") (pintype "passive"))
    )
    (net (code "40") (name "Net-(FR9-Pad2)") (class "Default")
      (node (ref "FR9") (pin "2") (pinfunction "2_2") (pintype "passive"))
      (node (ref "R204") (pin "1") (pinfunction "1_1") (pintype "passive"))
      (node (ref "R210") (pin "2") (pinfunction "2_2") (pintype "passive"))
      (node (ref "R212") (pin "1") (pinfunction "1_1") (pintype "passive"))
      (node (ref "R215") (pin "1") (pinfunction "1_1") (pintype "passive"))
    )
    (net (code "41") (name "Net-(IC36-CLKin)") (class "Default")
      (node (ref "C163") (pin "1") (pinfunction "1_1") (pintype "passive"))
      (node (ref "IC36") (pin "21") (pinfunction "CLKin_21") (pintype "passive"))
    )
    (net (code "42") (name "Net-(IC36-CLKin*)") (class "Default")
      (node (ref "C165") (pin "2") (pinfunction "2_2") (pintype "passive"))
      (node (ref "IC36") (pin "20") (pinfunction "CLKin*_20") (pintype "passive"))
    )
    (net (code "43") (name "Net-(IC36-OE)") (class "Default")
      (node (ref "IC36") (pin "24") (pinfunction "OE_24") (pintype "passive"))
      (node (ref "R205") (pin "1") (pinfunction "1_1") (pintype "passive"))
    )
    (net (code "44") (name "Net-(IC37-EN)") (class "Default")
      (node (ref "C181") (pin "2") (pinfunction "2_2") (pintype "passive"))
      (node (ref "C183") (pin "2") (pinfunction "2_2") (pintype "passive"))
      (node (ref "IC37") (pin "1") (pinfunction "IN_1") (pintype "input"))
      (node (ref "IC37") (pin "3") (pinfunction "EN_3") (pintype "input"))
      (node (ref "R215") (pin "2") (pinfunction "2_2") (pintype "passive"))
      (node (ref "R217") (pin "2") (pinfunction "2_2") (pintype "passive"))
    )
    (net (code "45") (name "Net-(IC37-OUT)") (class "Default")
      (node (ref "C182") (pin "2") (pinfunction "2_2") (pintype "passive"))
      (node (ref "C184") (pin "2") (pinfunction "2_2") (pintype "passive"))
      (node (ref "IC37") (pin "5") (pinfunction "OUT_5") (pintype "output"))
      (node (ref "R217") (pin "1") (pinfunction "1_1") (pintype "passive"))
      (node (ref "XO10") (pin "4") (pinfunction "VCC_4") (pintype "passive"))
    )
    (net (code "46") (name "Net-(IC40-D_SEL)") (class "Default")
      (node (ref "IC40") (pin "2") (pinfunction "D_SEL_2") (pintype "passive"))
      (node (ref "R228") (pin "2") (pinfunction "2_2") (pintype "passive"))
    )
    (net (code "47") (name "Net-(IC40-RESET_N)") (class "Default")
      (node (ref "IC40") (pin "8") (pinfunction "RESET_N_8") (pintype "passive"))
      (node (ref "R225") (pin "2") (pinfunction "2_2") (pintype "passive"))
    )
    (net (code "48") (name "Net-(IC40-RF_IN)") (class "Default")
      (node (ref "C190") (pin "2") (pinfunction "2_2") (pintype "passive"))
      (node (ref "IC40") (pin "11") (pinfunction "RF_IN_11") (pintype "passive"))
    )
    (net (code "49") (name "Net-(IC40-SAFEBOOT_N)") (class "Default")
      (node (ref "IC40") (pin "1") (pinfunction "SAFEBOOT_N_1") (pintype "passive"))
      (node (ref "R231") (pin "2") (pinfunction "2_2") (pintype "passive"))
    )
    (net (code "50") (name "Net-(IC40-V_BCKP)") (class "Default")
      (node (ref "C195") (pin "1") (pinfunction "1_1") (pintype "passive"))
      (node (ref "IC40") (pin "22") (pinfunction "V_BCKP_22") (pintype "passive"))
      (node (ref "R230") (pin "1") (pinfunction "1_1") (pintype "passive"))
      (node (ref "R232") (pin "1") (pinfunction "1_1") (pintype "passive"))
    )
    (net (code "51") (name "Net-(J35-X)") (class "Default")
      (node (ref "J35") (pin "1") (pinfunction "X_1") (pintype "passive"))
      (node (ref "R207") (pin "1") (pinfunction "1_1") (pintype "passive"))
    )
    (net (code "52") (name "Net-(J39-Pad2)") (class "Default")
      (node (ref "J39") (pin "2") (pinfunction "2_2") (pintype "passive"))
      (node (ref "R211") (pin "1") (pinfunction "1_1") (pintype "passive"))
    )
    (net (code "53") (name "Net-(R212-Pad2)") (class "Default")
      (node (ref "R212") (pin "2") (pinfunction "2_2") (pintype "passive"))
      (node (ref "R214") (pin "1") (pinfunction "1_1") (pintype "passive"))
    )
    (net (code "54") (name "Net-(R218-Pad1)") (class "Default")
      (node (ref "R218") (pin "1") (pinfunction "1_1") (pintype "passive"))
      (node (ref "R219") (pin "2") (pinfunction "2_2") (pintype "passive"))
      (node (ref "R220") (pin "2") (pinfunction "2_2") (pintype "passive"))
    )
    (net (code "55") (name "Net-(XO6-Output)") (class "Default")
      (node (ref "R203") (pin "2") (pinfunction "2_2") (pintype "passive"))
      (node (ref "XO6") (pin "3") (pinfunction "Output_3") (pintype "output"))
    )
    (net (code "56") (name "Net-(XO6-Vcc)") (class "Default")
      (node (ref "C160") (pin "2") (pinfunction "2_2") (pintype "passive"))
      (node (ref "C161") (pin "2") (pinfunction "2_2") (pintype "passive"))
      (node (ref "C162") (pin "1") (pinfunction "1_1") (pintype "passive"))
      (node (ref "R204") (pin "2") (pinfunction "2_2") (pintype "passive"))
      (node (ref "XO6") (pin "4") (pinfunction "Vcc_4") (pintype "power_in"))
    )
    (net (code "57") (name "Net-(XO7-OUT)") (class "Default")
      (node (ref "R209") (pin "2") (pinfunction "2_2") (pintype "passive"))
      (node (ref "XO7") (pin "4") (pinfunction "OUT_4") (pintype "passive"))
      (node (ref "XO8") (pin "3") (pinfunction "OUT_3") (pintype "passive"))
    )
    (net (code "58") (name "Net-(XO7-TRI-ST.)") (class "Default")
      (node (ref "R208") (pin "1") (pinfunction "1_1") (pintype "passive"))
      (node (ref "XO7") (pin "6") (pinfunction "TRI-ST._6") (pintype "passive"))
    )
    (net (code "59") (name "Net-(XO7-VDD)") (class "Default")
      (node (ref "C166") (pin "2") (pinfunction "2_2") (pintype "passive"))
      (node (ref "C167") (pin "2") (pinfunction "2_2") (pintype "passive"))
      (node (ref "R208") (pin "2") (pinfunction "2_2") (pintype "passive"))
      (node (ref "R210") (pin "1") (pinfunction "1_1") (pintype "passive"))
      (node (ref "XO7") (pin "5") (pinfunction "VDD_5") (pintype "passive"))
      (node (ref "XO8") (pin "4") (pinfunction "VDD_4") (pintype "passive"))
    )
    (net (code "60") (name "Net-(XO9-RF_OUT)") (class "Default")
      (node (ref "R213") (pin "1") (pinfunction "1_1") (pintype "passive"))
      (node (ref "XO9") (pin "6") (pinfunction "RF_OUT_6") (pintype "output"))
    )
    (net (code "61") (name "Net-(XO9-VCC)") (class "Default")
      (node (ref "C172") (pin "2") (pinfunction "2_2") (pintype "passive"))
      (node (ref "C173") (pin "2") (pinfunction "2_2") (pintype "passive"))
      (node (ref "R214") (pin "2") (pinfunction "2_2") (pintype "passive"))
      (node (ref "XO9") (pin "9") (pinfunction "VCC_9") (pintype "power_in"))
    )
    (net (code "62") (name "Net-(XO9-VC_FILTER)") (class "Default")
      (node (ref "C174") (pin "2") (pinfunction "2_2") (pintype "passive"))
      (node (ref "XO9") (pin "7") (pinfunction "VC_FILTER_7") (pintype "input"))
    )
    (net (code "63") (name "Net-(XO10-OUT)") (class "Default")
      (node (ref "R216") (pin "2") (pinfunction "2_2") (pintype "passive"))
      (node (ref "XO10") (pin "3") (pinfunction "OUT_3") (pintype "passive"))
    )
    (net (code "64") (name "VCC3P0_BATT") (class "Default")
      (node (ref "J43") (pin "2") (pinfunction "2_2") (pintype "passive"))
      (node (ref "R230") (pin "2") (pinfunction "2_2") (pintype "passive"))
    )
    (net (code "65") (name "VCC3P3") (class "Default")
      (node (ref "C185") (pin "1") (pinfunction "1_1") (pintype "passive"))
      (node (ref "C186") (pin "1") (pinfunction "1_1") (pintype "passive"))
      (node (ref "C191") (pin "1") (pinfunction "1_1") (pintype "passive"))
      (node (ref "C193") (pin "1") (pinfunction "1_1") (pintype "passive"))
      (node (ref "C194") (pin "1") (pinfunction "1_1") (pintype "passive"))
      (node (ref "IC38") (pin "1") (pinfunction "VCCA_1") (pintype "power_in"))
      (node (ref "IC38") (pin "5") (pinfunction "DIR_5") (pintype "input"))
      (node (ref "IC38") (pin "6") (pinfunction "VCCB_6") (pintype "power_in"))
      (node (ref "IC39") (pin "9") (pinfunction "VCC_9") (pintype "power_in"))
      (node (ref "IC41") (pin "1") (pinfunction "VCCA_1") (pintype "power_in"))
      (node (ref "IC41") (pin "6") (pinfunction "VCCB_6") (pintype "power_in"))
      (node (ref "R224") (pin "1") (pinfunction "1_1") (pintype "passive"))
    )
    (net (code "66") (name "VCC3P3_CLK2") (class "Default")
      (node (ref "FR10") (pin "1") (pinfunction "1_1") (pintype "passive"))
      (node (ref "FR11") (pin "1") (pinfunction "1_1") (pintype "passive"))
      (node (ref "FR12") (pin "1") (pinfunction "1_1") (pintype "passive"))
      (node (ref "FR9") (pin "1") (pinfunction "1_1") (pintype "passive"))
    )
    (net (code "67") (name "VCC3P3_GNSS") (class "Default")
      (node (ref "C188") (pin "2") (pinfunction "2_2") (pintype "passive"))
      (node (ref "C189") (pin "2") (pinfunction "2_2") (pintype "passive"))
      (node (ref "C196") (pin "2") (pinfunction "2_2") (pintype "passive"))
      (node (ref "C197") (pin "1") (pinfunction "1_1") (pintype "passive"))
      (node (ref "FR12") (pin "2") (pinfunction "2_2") (pintype "passive"))
      (node (ref "IC40") (pin "23") (pinfunction "VCC_23") (pintype "passive"))
      (node (ref "R219") (pin "1") (pinfunction "1_1") (pintype "passive"))
      (node (ref "R232") (pin "2") (pinfunction "2_2") (pintype "passive"))
    )
    (net (code "68") (name "VCC3P3_LMK10") (class "Default")
      (node (ref "C168") (pin "2") (pinfunction "2_2") (pintype "passive"))
      (node (ref "C169") (pin "2") (pinfunction "2_2") (pintype "passive"))
      (node (ref "C170") (pin "2") (pinfunction "2_2") (pintype "passive"))
      (node (ref "C171") (pin "2") (pinfunction "2_2") (pintype "passive"))
      (node (ref "FR10") (pin "2") (pinfunction "2_2") (pintype "passive"))
      (node (ref "IC36") (pin "23") (pinfunction "Vdd_23") (pintype "passive"))
      (node (ref "IC36") (pin "8") (pinfunction "Vdd_8") (pintype "passive"))
      (node (ref "R205") (pin "2") (pinfunction "2_2") (pintype "passive"))
    )
    (net (code "69") (name "VCC3P3_LMK10_VDDO") (class "Default")
      (node (ref "C175") (pin "2") (pinfunction "2_2") (pintype "passive"))
      (node (ref "C176") (pin "2") (pinfunction "2_2") (pintype "passive"))
      (node (ref "C177") (pin "2") (pinfunction "2_2") (pintype "passive"))
      (node (ref "C178") (pin "2") (pinfunction "2_2") (pintype "passive"))
      (node (ref "C179") (pin "2") (pinfunction "2_2") (pintype "passive"))
      (node (ref "C180") (pin "2") (pinfunction "2_2") (pintype "passive"))
      (node (ref "FR11") (pin "2") (pinfunction "2_2") (pintype "passive"))
      (node (ref "IC36") (pin "14") (pinfunction "Vddo_14") (pintype "passive"))
      (node (ref "IC36") (pin "18") (pinfunction "Vddo_18") (pintype "passive"))
      (node (ref "IC36") (pin "2") (pinfunction "Vddo_2") (pintype "passive"))
      (node (ref "IC36") (pin "6") (pinfunction "Vddo_6") (pintype "passive"))
    )
    (net (code "70") (name "unconnected-(IC36-CLKout1-Pad5)") (class "Default")
      (node (ref "IC36") (pin "5") (pinfunction "CLKout1_5") (pintype "passive+no_connect"))
    )
    (net (code "71") (name "unconnected-(IC36-OSCin-Pad9)") (class "Default")
      (node (ref "IC36") (pin "9") (pinfunction "OSCin_9") (pintype "passive+no_connect"))
    )
    (net (code "72") (name "unconnected-(IC36-OSCout-Pad10)") (class "Default")
      (node (ref "IC36") (pin "10") (pinfunction "OSCout_10") (pintype "passive+no_connect"))
    )
    (net (code "73") (name "unconnected-(IC37-NC-Pad4)") (class "Default")
      (node (ref "IC37") (pin "4") (pinfunction "NC_4") (pintype "passive+no_connect"))
    )
    (net (code "74") (name "unconnected-(IC39-HSD2--Pad6)") (class "Default")
      (node (ref "IC39") (pin "6") (pinfunction "HSD2-_6") (pintype "passive+no_connect"))
    )
    (net (code "75") (name "unconnected-(IC40-GEOFENCE_STAT{slash}RESV-Pad16)") (class "Default")
      (node (ref "IC40") (pin "16") (pinfunction "GEOFENCE_STAT/RESV_16") (pintype "passive+no_connect"))
    )
    (net (code "76") (name "unconnected-(IC40-LNA_EN{slash}RESV-Pad14)") (class "Default")
      (node (ref "IC40") (pin "14") (pinfunction "LNA_EN/RESV_14") (pintype "passive+no_connect"))
    )
    (net (code "77") (name "unconnected-(IC40-RESV-Pad17)") (class "Default")
      (node (ref "IC40") (pin "17") (pinfunction "RESV_17") (pintype "passive+no_connect"))
    )
    (net (code "78") (name "unconnected-(IC40-RTK_STAT{slash}RESV-Pad15)") (class "Default")
      (node (ref "IC40") (pin "15") (pinfunction "RTK_STAT/RESV_15") (pintype "passive+no_connect"))
    )
    (net (code "79") (name "unconnected-(JMP2-Pad1)") (class "Default")
      (node (ref "JMP2") (pin "1") (pinfunction "1_1") (pintype "passive"))
    )
    (net (code "80") (name "unconnected-(JMP2-Pad2)") (class "Default")
      (node (ref "JMP2") (pin "2") (pinfunction "2_2") (pintype "passive"))
    )
    (net (code "81") (name "unconnected-(JMP3-Pad1)") (class "Default")
      (node (ref "JMP3") (pin "1") (pinfunction "1_1") (pintype "passive"))
    )
    (net (code "82") (name "unconnected-(JMP3-Pad2)") (class "Default")
      (node (ref "JMP3") (pin "2") (pinfunction "2_2") (pintype "passive"))
    )
    (net (code "83") (name "unconnected-(JMP4-Pad1)") (class "Default")
      (node (ref "JMP4") (pin "1") (pinfunction "1_1") (pintype "passive"))
    )
    (net (code "84") (name "unconnected-(JMP4-Pad2)") (class "Default")
      (node (ref "JMP4") (pin "2") (pinfunction "2_2") (pintype "passive"))
    )
    (net (code "85") (name "unconnected-(JMP5-Pad1)") (class "Default")
      (node (ref "JMP5") (pin "1") (pinfunction "1_1") (pintype "passive"))
    )
    (net (code "86") (name "unconnected-(JMP5-Pad2)") (class "Default")
      (node (ref "JMP5") (pin "2") (pinfunction "2_2") (pintype "passive"))
    )
    (net (code "87") (name "unconnected-(JMP6-Pad1)") (class "Default")
      (node (ref "JMP6") (pin "1") (pinfunction "1_1") (pintype "passive"))
    )
    (net (code "88") (name "unconnected-(JMP6-Pad2)") (class "Default")
      (node (ref "JMP6") (pin "2") (pinfunction "2_2") (pintype "passive"))
    )
    (net (code "89") (name "unconnected-(JMP7-Pad1)") (class "Default")
      (node (ref "JMP7") (pin "1") (pinfunction "1_1") (pintype "passive"))
    )
    (net (code "90") (name "unconnected-(JMP7-Pad2)") (class "Default")
      (node (ref "JMP7") (pin "2") (pinfunction "2_2") (pintype "passive"))
    )
    (net (code "91") (name "unconnected-(XO7-T.S.-Pad3)") (class "Default")
      (node (ref "XO7") (pin "3") (pinfunction "T.S._3") (pintype "passive+no_connect"))
    )
    (net (code "92") (name "unconnected-(XO9-NC-Pad2)") (class "Default")
      (node (ref "XO9") (pin "2") (pinfunction "NC_2") (pintype "passive+no_connect"))
    )
    (net (code "93") (name "unconnected-(XO9-NC-Pad3)") (class "Default")
      (node (ref "XO9") (pin "3") (pinfunction "NC_3") (pintype "passive+no_connect"))
    )
    (net (code "94") (name "unconnected-(XO9-NC-Pad5)") (class "Default")
      (node (ref "XO9") (pin "5") (pinfunction "NC_5") (pintype "passive+no_connect"))
    )
    (net (code "95") (name "unconnected-(XO9-NC-Pad8)") (class "Default")
      (node (ref "XO9") (pin "8") (pinfunction "NC_8") (pintype "passive+no_connect"))
    )
    (net (code "96") (name "unconnected-(XO9-NC-Pad10)") (class "Default")
      (node (ref "XO9") (pin "10") (pinfunction "NC_10") (pintype "passive+no_connect"))
    )
  )
)
